# Sheet1.net
KiCad netlist of a schematic drawn in Altium Designer
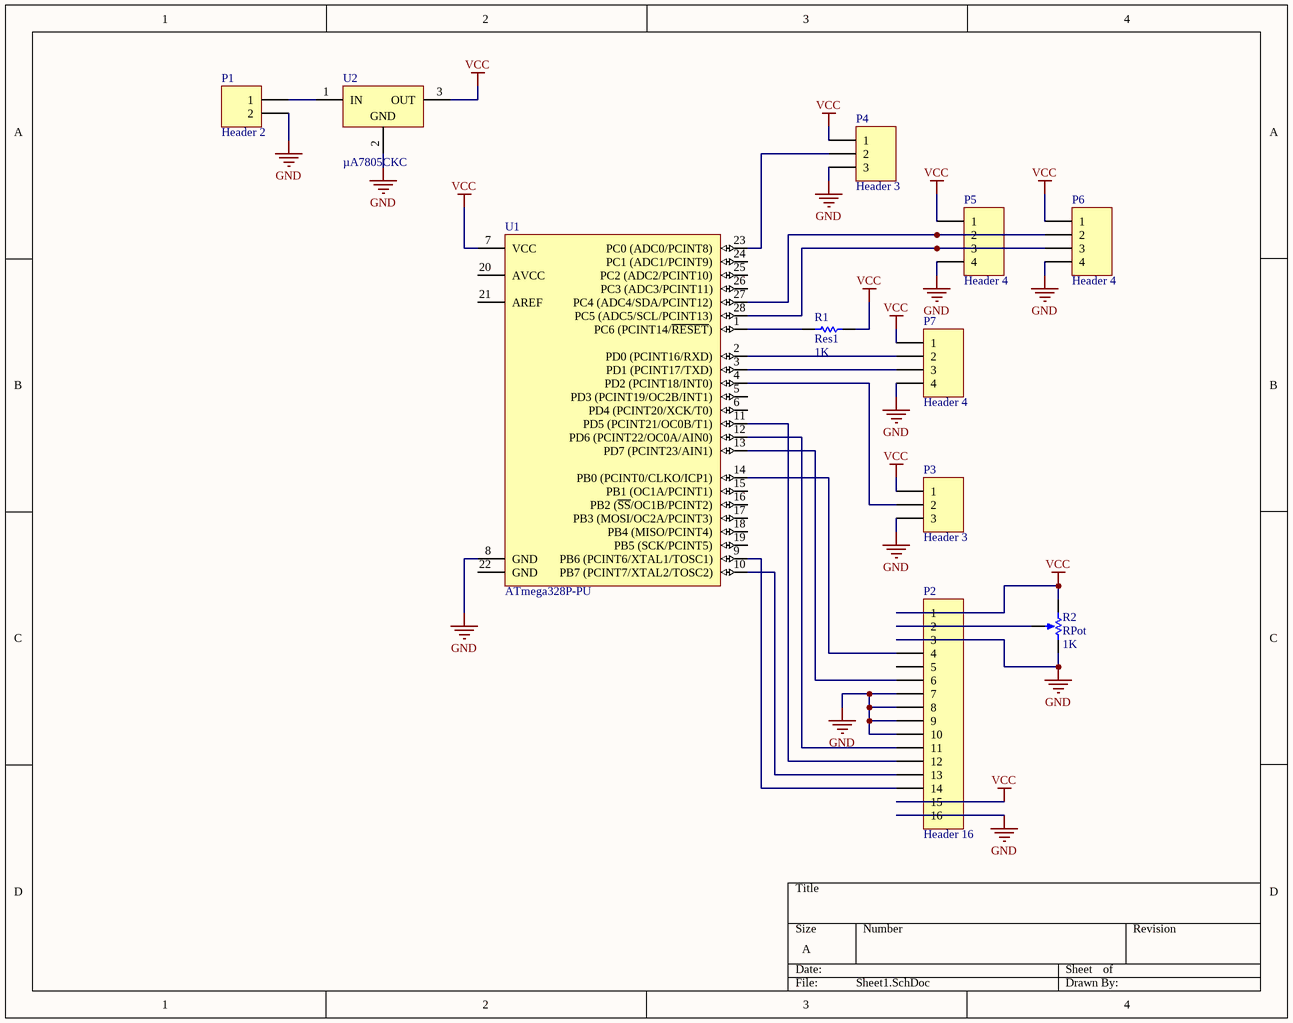
[diagram p0: Sheet1.SchDoc]

(export (version "E")
  (design (tool "Eeschema 10.0.6"))
  (components
    (comp (ref "P1")
      (value "Header 2")
      (footprint "HDR1X2")
      (description "Header, 2-Pin")
      (fields (field (name "PUBLISHER") "Altium Limited"))
      (libsource (lib "Miscellaneous Connectors") (part "Header 2"))
    )
    (comp (ref "P2")
      (value "Header 16")
      (footprint "HDR1X16")
      (description "Header, 16-Pin")
      (fields (field (name "PUBLISHER") "Altium Limited"))
      (libsource (lib "Miscellaneous Connectors") (part "Header 16"))
    )
    (comp (ref "P3")
      (value "Header 3")
      (footprint "HDR1X3")
      (description "Header, 3-Pin")
      (fields (field (name "PUBLISHER") "Altium Limited"))
      (libsource (lib "Miscellaneous Connectors") (part "Header 3"))
    )
    (comp (ref "P4")
      (value "Header 3")
      (footprint "HDR1X3")
      (description "Header, 3-Pin")
      (fields (field (name "PUBLISHER") "Altium Limited"))
      (libsource (lib "Miscellaneous Connectors") (part "Header 3"))
    )
    (comp (ref "P5")
      (value "Header 4")
      (footprint "HDR1X4")
      (description "Header, 4-Pin")
      (fields (field (name "PUBLISHER") "Altium Limited"))
      (libsource (lib "Miscellaneous Connectors") (part "Header 4"))
    )
    (comp (ref "P6")
      (value "Header 4")
      (footprint "HDR1X4")
      (description "Header, 4-Pin")
      (fields (field (name "PUBLISHER") "Altium Limited"))
      (libsource (lib "Miscellaneous Connectors") (part "Header 4"))
    )
    (comp (ref "P7")
      (value "Header 4")
      (footprint "HDR1X4")
      (description "Header, 4-Pin")
      (fields (field (name "PUBLISHER") "Altium Limited"))
      (libsource (lib "Miscellaneous Connectors") (part "Header 4"))
    )
    (comp (ref "R1")
      (value "Res1")
      (footprint "AXIAL-0.3")
      (description "Resistor")
      (fields (field (name "ALTIUM_VALUE") "1K") (field (name "PUBLISHER") "Altium Limited"))
      (libsource (lib "Miscellaneous Devices") (part "Res1"))
    )
    (comp (ref "R2")
      (value "RPot")
      (footprint "VR5")
      (description "Potentiometer")
      (fields (field (name "ALTIUM_VALUE") "1K") (field (name "PUBLISHER") "Altium Limited"))
      (libsource (lib "Miscellaneous Devices") (part "RPot"))
    )
    (comp (ref "U1")
      (value "ATmega328P-PU")
      (footprint "28P3")
      (fields (field (name "PUBLISHER") "Altium Limited"))
      (libsource (lib "Atmel Microcontroller 8-Bit megaAVR") (part "ATmega328P-PU"))
    )
    (comp (ref "U2")
      (value "µA7805CKC")
      (footprint "KC03")
      (description "Positive-Voltage Regulator")
      (fields (field (name "PUBLISHER") "Altium Limited"))
      (libsource (lib "TI Power Mgt Voltage Regulator") (part "µA7805CKC"))
    )
  )
  (nets
    (net (code "1") (name "GND") (class "Default")
      (node (ref "P1") (pin "2") (pinfunction "2_2") (pintype "passive"))
      (node (ref "P2") (pin "10") (pinfunction "10_10") (pintype "passive"))
      (node (ref "P2") (pin "16") (pinfunction "16_16") (pintype "passive"))
      (node (ref "P2") (pin "3") (pinfunction "3_3") (pintype "passive"))
      (node (ref "P2") (pin "7") (pinfunction "7_7") (pintype "passive"))
      (node (ref "P2") (pin "8") (pinfunction "8_8") (pintype "passive"))
      (node (ref "P2") (pin "9") (pinfunction "9_9") (pintype "passive"))
      (node (ref "P3") (pin "3") (pinfunction "3_3") (pintype "passive"))
      (node (ref "P4") (pin "3") (pinfunction "3_3") (pintype "passive"))
      (node (ref "P5") (pin "4") (pinfunction "4_4") (pintype "passive"))
      (node (ref "P6") (pin "4") (pinfunction "4_4") (pintype "passive"))
      (node (ref "P7") (pin "4") (pinfunction "4_4") (pintype "passive"))
      (node (ref "R2") (pin "2") (pinfunction "BOT_2") (pintype "passive"))
      (node (ref "U1") (pin "8") (pinfunction "GND_8") (pintype "power_in"))
      (node (ref "U2") (pin "2") (pinfunction "GND_2") (pintype "power_in"))
    )
    (net (code "2") (name "Net-(R2-TAP)") (class "Default")
      (node (ref "P2") (pin "2") (pinfunction "2_2") (pintype "passive"))
      (node (ref "R2") (pin "3") (pinfunction "TAP_3") (pintype "passive"))
    )
    (net (code "3") (name "Net-(U1-PB0_(PCINT0{slash}CLKO{slash}ICP1))") (class "Default")
      (node (ref "P2") (pin "4") (pinfunction "4_4") (pintype "passive"))
      (node (ref "U1") (pin "14") (pinfunction "PB0_(PCINT0/CLKO/ICP1)_14") (pintype "bidirectional"))
    )
    (net (code "4") (name "Net-(U1-PB6_(PCINT6{slash}XTAL1{slash}TOSC1))") (class "Default")
      (node (ref "P2") (pin "14") (pinfunction "14_14") (pintype "passive"))
      (node (ref "U1") (pin "9") (pinfunction "PB6_(PCINT6/XTAL1/TOSC1)_9") (pintype "bidirectional"))
    )
    (net (code "5") (name "Net-(U1-PB7_(PCINT7{slash}XTAL2{slash}TOSC2))") (class "Default")
      (node (ref "P2") (pin "13") (pinfunction "13_13") (pintype "passive"))
      (node (ref "U1") (pin "10") (pinfunction "PB7_(PCINT7/XTAL2/TOSC2)_10") (pintype "bidirectional"))
    )
    (net (code "6") (name "Net-(U1-PC0_(ADC0{slash}PCINT8))") (class "Default")
      (node (ref "P4") (pin "2") (pinfunction "2_2") (pintype "passive"))
      (node (ref "U1") (pin "23") (pinfunction "PC0_(ADC0/PCINT8)_23") (pintype "bidirectional"))
    )
    (net (code "7") (name "Net-(U1-PC4_(ADC4{slash}SDA{slash}PCINT12))") (class "Default")
      (node (ref "P5") (pin "2") (pinfunction "2_2") (pintype "passive"))
      (node (ref "P6") (pin "2") (pinfunction "2_2") (pintype "passive"))
      (node (ref "U1") (pin "27") (pinfunction "PC4_(ADC4/SDA/PCINT12)_27") (pintype "bidirectional"))
    )
    (net (code "8") (name "Net-(U1-PC5_(ADC5{slash}SCL{slash}PCINT13))") (class "Default")
      (node (ref "P5") (pin "3") (pinfunction "3_3") (pintype "passive"))
      (node (ref "P6") (pin "3") (pinfunction "3_3") (pintype "passive"))
      (node (ref "U1") (pin "28") (pinfunction "PC5_(ADC5/SCL/PCINT13)_28") (pintype "bidirectional"))
    )
    (net (code "9") (name "Net-(U1-PC6_(PCINT14{slash}~{RESET}))") (class "Default")
      (node (ref "R1") (pin "1") (pinfunction "1_1") (pintype "passive"))
      (node (ref "U1") (pin "1") (pinfunction "PC6_(PCINT14/~{RESET})_1") (pintype "bidirectional"))
    )
    (net (code "10") (name "Net-(U1-PD0_(PCINT16{slash}RXD))") (class "Default")
      (node (ref "P7") (pin "2") (pinfunction "2_2") (pintype "passive"))
      (node (ref "U1") (pin "2") (pinfunction "PD0_(PCINT16/RXD)_2") (pintype "bidirectional"))
    )
    (net (code "11") (name "Net-(U1-PD1_(PCINT17{slash}TXD))") (class "Default")
      (node (ref "P7") (pin "3") (pinfunction "3_3") (pintype "passive"))
      (node (ref "U1") (pin "3") (pinfunction "PD1_(PCINT17/TXD)_3") (pintype "bidirectional"))
    )
    (net (code "12") (name "Net-(U1-PD2_(PCINT18{slash}INT0))") (class "Default")
      (node (ref "P3") (pin "2") (pinfunction "2_2") (pintype "passive"))
      (node (ref "U1") (pin "4") (pinfunction "PD2_(PCINT18/INT0)_4") (pintype "bidirectional"))
    )
    (net (code "13") (name "Net-(U1-PD5_(PCINT21{slash}OC0B{slash}T1))") (class "Default")
      (node (ref "P2") (pin "12") (pinfunction "12_12") (pintype "passive"))
      (node (ref "U1") (pin "11") (pinfunction "PD5_(PCINT21/OC0B/T1)_11") (pintype "bidirectional"))
    )
    (net (code "14") (name "Net-(U1-PD6_(PCINT22{slash}OC0A{slash}AIN0))") (class "Default")
      (node (ref "P2") (pin "11") (pinfunction "11_11") (pintype "passive"))
      (node (ref "U1") (pin "12") (pinfunction "PD6_(PCINT22/OC0A/AIN0)_12") (pintype "bidirectional"))
    )
    (net (code "15") (name "Net-(U1-PD7_(PCINT23{slash}AIN1))") (class "Default")
      (node (ref "P2") (pin "6") (pinfunction "6_6") (pintype "passive"))
      (node (ref "U1") (pin "13") (pinfunction "PD7_(PCINT23/AIN1)_13") (pintype "bidirectional"))
    )
    (net (code "16") (name "Net-(U2-IN)") (class "Default")
      (node (ref "P1") (pin "1") (pinfunction "1_1") (pintype "passive"))
      (node (ref "U2") (pin "1") (pinfunction "IN_1") (pintype "power_in"))
    )
    (net (code "17") (name "VCC") (class "Default")
      (node (ref "P2") (pin "1") (pinfunction "1_1") (pintype "passive"))
      (node (ref "P2") (pin "15") (pinfunction "15_15") (pintype "passive"))
      (node (ref "P3") (pin "1") (pinfunction "1_1") (pintype "passive"))
      (node (ref "P4") (pin "1") (pinfunction "1_1") (pintype "passive"))
      (node (ref "P5") (pin "1") (pinfunction "1_1") (pintype "passive"))
      (node (ref "P6") (pin "1") (pinfunction "1_1") (pintype "passive"))
      (node (ref "P7") (pin "1") (pinfunction "1_1") (pintype "passive"))
      (node (ref "R1") (pin "2") (pinfunction "2_2") (pintype "passive"))
      (node (ref "R2") (pin "1") (pinfunction "TOP_1") (pintype "passive"))
      (node (ref "U1") (pin "7") (pinfunction "VCC_7") (pintype "power_in"))
      (node (ref "U2") (pin "3") (pinfunction "OUT_3") (pintype "power_in"))
    )
    (net (code "18") (name "unconnected-(P2-Pad5)") (class "Default")
      (node (ref "P2") (pin "5") (pinfunction "5_5") (pintype "passive"))
    )
    (net (code "19") (name "unconnected-(U1-AREF-Pad21)") (class "Default")
      (node (ref "U1") (pin "21") (pinfunction "AREF_21") (pintype "power_in"))
    )
    (net (code "20") (name "unconnected-(U1-AVCC-Pad20)") (class "Default")
      (node (ref "U1") (pin "20") (pinfunction "AVCC_20") (pintype "power_in"))
    )
    (net (code "21") (name "unconnected-(U1-GND-Pad22)") (class "Default")
      (node (ref "U1") (pin "22") (pinfunction "GND_22") (pintype "power_in"))
    )
    (net (code "22") (name "unconnected-(U1-PB1_(OC1A{slash}PCINT1)-Pad15)") (class "Default")
      (node (ref "U1") (pin "15") (pinfunction "PB1_(OC1A/PCINT1)_15") (pintype "bidirectional"))
    )
    (net (code "23") (name "unconnected-(U1-PB2_(~{SS}{slash}OC1B{slash}PCINT2)-Pad16)") (class "Default")
      (node (ref "U1") (pin "16") (pinfunction "PB2_(~{SS}/OC1B/PCINT2)_16") (pintype "bidirectional"))
    )
    (net (code "24") (name "unconnected-(U1-PB3_(MOSI{slash}OC2A{slash}PCINT3)-Pad17)") (class "Default")
      (node (ref "U1") (pin "17") (pinfunction "PB3_(MOSI/OC2A/PCINT3)_17") (pintype "bidirectional"))
    )
    (net (code "25") (name "unconnected-(U1-PB4_(MISO{slash}PCINT4)-Pad18)") (class "Default")
      (node (ref "U1") (pin "18") (pinfunction "PB4_(MISO/PCINT4)_18") (pintype "bidirectional"))
    )
    (net (code "26") (name "unconnected-(U1-PB5_(SCK{slash}PCINT5)-Pad19)") (class "Default")
      (node (ref "U1") (pin "19") (pinfunction "PB5_(SCK/PCINT5)_19") (pintype "bidirectional"))
    )
    (net (code "27") (name "unconnected-(U1-PC1_(ADC1{slash}PCINT9)-Pad24)") (class "Default")
      (node (ref "U1") (pin "24") (pinfunction "PC1_(ADC1/PCINT9)_24") (pintype "bidirectional"))
    )
    (net (code "28") (name "unconnected-(U1-PC2_(ADC2{slash}PCINT10)-Pad25)") (class "Default")
      (node (ref "U1") (pin "25") (pinfunction "PC2_(ADC2/PCINT10)_25") (pintype "bidirectional"))
    )
    (net (code "29") (name "unconnected-(U1-PC3_(ADC3{slash}PCINT11)-Pad26)") (class "Default")
      (node (ref "U1") (pin "26") (pinfunction "PC3_(ADC3/PCINT11)_26") (pintype "bidirectional"))
    )
    (net (code "30") (name "unconnected-(U1-PD3_(PCINT19{slash}OC2B{slash}INT1)-Pad5)") (class "Default")
      (node (ref "U1") (pin "5") (pinfunction "PD3_(PCINT19/OC2B/INT1)_5") (pintype "bidirectional"))
    )
    (net (code "31") (name "unconnected-(U1-PD4_(PCINT20{slash}XCK{slash}T0)-Pad6)") (class "Default")
      (node (ref "U1") (pin "6") (pinfunction "PD4_(PCINT20/XCK/T0)_6") (pintype "bidirectional"))
    )
  )
)
